# buttons.net
KiCad netlist of a schematic drawn in Altium Designer
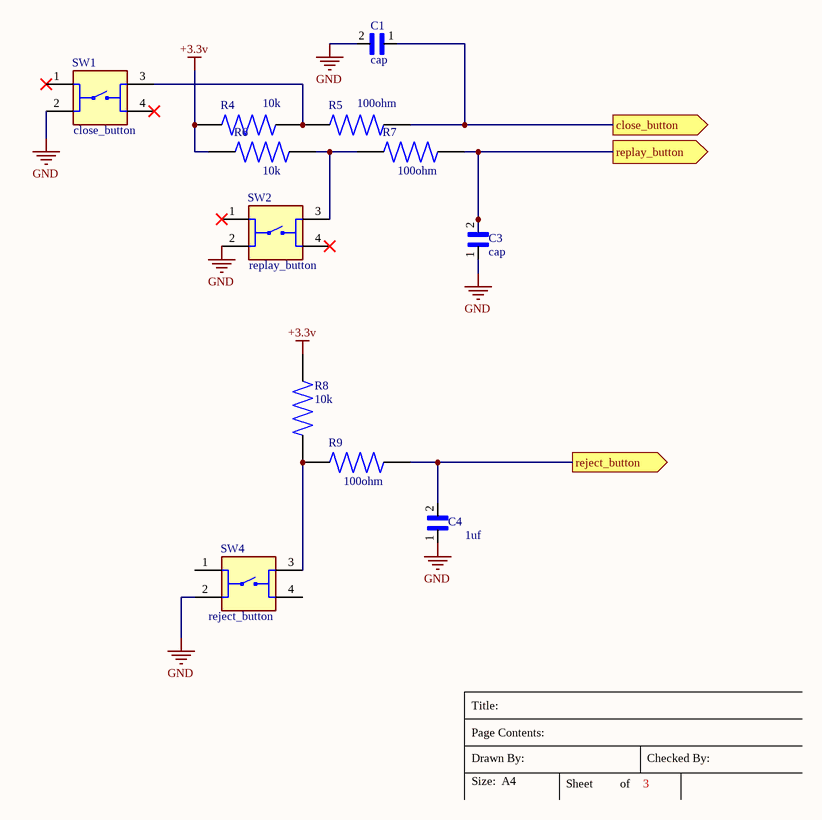
[diagram p0: buttons.SchDoc]

(export (version "E")
  (design (tool "Eeschema 10.0.6"))
  (components
    (comp (ref "C1")
      (value "cap")
      (footprint "cap")
      (description "Lead Capacitor X7R_EIA_ with Capacitance: 0.10F and Rated Voltage: 1000Vdc")
      (fields (field (name "MF") "Murata") (field (name "MP") "RDER73A104K5E1H03A"))
      (libsource (lib "") (part "cap_1"))
    )
    (comp (ref "C3")
      (value "cap")
      (footprint "cap")
      (description "Lead Capacitor X7R_EIA_ with Capacitance: 0.10F and Rated Voltage: 1000Vdc")
      (fields (field (name "MF") "Murata") (field (name "MP") "RDER73A104K5E1H03A"))
      (libsource (lib "Schlib_circuit_de_puissance") (part "cap"))
    )
    (comp (ref "C4")
      (value "1uf")
      (footprint "cap")
      (description "Lead Capacitor X7R_EIA_ with Capacitance: 0.10F and Rated Voltage: 1000Vdc")
      (fields (field (name "MF") "Murata") (field (name "MP") "RDER73A104K5E1H03A"))
      (libsource (lib "Schlib_circuit_de_puissance") (part "cap"))
    )
    (comp (ref "R4")
      (value "10k")
      (footprint "resistance")
      (fields
        (field (name "MP") "CBT50J5R1")
        (field (name "MF") "TE Connectivity / AMP")
        (field (name "Comment") "resistance")
      )
      (libsource (lib "Schlib_circuit_de_puissance") (part "resistance"))
    )
    (comp (ref "R5")
      (value "100ohm")
      (footprint "resistance")
      (fields
        (field (name "MP") "CBT50J5R1")
        (field (name "MF") "TE Connectivity / AMP")
        (field (name "Comment") "resistance")
      )
      (libsource (lib "Schlib_circuit_de_puissance") (part "resistance"))
    )
    (comp (ref "R6")
      (value "10k")
      (footprint "resistance")
      (fields
        (field (name "MP") "CBT50J5R1")
        (field (name "MF") "TE Connectivity / AMP")
        (field (name "Comment") "resistance")
      )
      (libsource (lib "Schlib_circuit_de_puissance") (part "resistance"))
    )
    (comp (ref "R7")
      (value "100ohm")
      (footprint "resistance")
      (fields
        (field (name "MP") "CBT50J5R1")
        (field (name "MF") "TE Connectivity / AMP")
        (field (name "Comment") "resistance")
      )
      (libsource (lib "Schlib_circuit_de_puissance") (part "resistance"))
    )
    (comp (ref "R8")
      (value "10k")
      (footprint "resistance")
      (fields
        (field (name "MP") "CBT50J5R1")
        (field (name "MF") "TE Connectivity / AMP")
        (field (name "Comment") "resistance")
      )
      (libsource (lib "Schlib_circuit_de_puissance") (part "resistance"))
    )
    (comp (ref "R9")
      (value "100ohm")
      (footprint "resistance")
      (fields
        (field (name "MP") "CBT50J5R1")
        (field (name "MF") "TE Connectivity / AMP")
        (field (name "Comment") "resistance")
      )
      (libsource (lib "Schlib_circuit_de_puissance") (part "resistance"))
    )
    (comp (ref "SW1")
      (value "close_button")
      (footprint "push_button_pcb")
      (description "Switch Push Button OFF (ON) SPST Round Button 0.05A 24VDC Momentary Contact PC Pins Thru-Hole")
      (fields (field (name "MP") "1825910-6") (field (name "MF") "TE Connectivity"))
      (libsource (lib "Schlib_circuit_de_puissance") (part "push_button"))
    )
    (comp (ref "SW2")
      (value "replay_button")
      (footprint "push_button_pcb")
      (description "Switch Push Button OFF (ON) SPST Round Button 0.05A 24VDC Momentary Contact PC Pins Thru-Hole")
      (fields (field (name "MP") "1825910-6") (field (name "MF") "TE Connectivity"))
      (libsource (lib "Schlib_circuit_de_puissance") (part "push_button"))
    )
    (comp (ref "SW4")
      (value "reject_button")
      (footprint "push_button_pcb")
      (description "Switch Push Button OFF (ON) SPST Round Button 0.05A 24VDC Momentary Contact PC Pins Thru-Hole")
      (fields (field (name "MP") "1825910-6") (field (name "MF") "TE Connectivity"))
      (libsource (lib "Schlib_circuit_de_puissance") (part "push_button"))
    )
  )
  (nets
    (net (code "1") (name "+3.3v") (class "Default")
      (node (ref "R4") (pin "2") (pinfunction "2_2") (pintype "passive"))
      (node (ref "R6") (pin "2") (pinfunction "2_2") (pintype "passive"))
      (node (ref "R8") (pin "1") (pinfunction "1_1") (pintype "passive"))
    )
    (net (code "2") (name "/close_button") (class "Default")
      (node (ref "C1") (pin "1") (pinfunction "1_1") (pintype "passive"))
      (node (ref "R5") (pin "1") (pinfunction "1_1") (pintype "passive"))
    )
    (net (code "3") (name "/reject_button") (class "Default")
      (node (ref "C4") (pin "2") (pinfunction "2_2") (pintype "passive"))
      (node (ref "R9") (pin "1") (pinfunction "1_1") (pintype "passive"))
    )
    (net (code "4") (name "/replay_button") (class "Default")
      (node (ref "C3") (pin "2") (pinfunction "2_2") (pintype "passive"))
      (node (ref "R7") (pin "1") (pinfunction "1_1") (pintype "passive"))
    )
    (net (code "5") (name "GND") (class "Default")
      (node (ref "C1") (pin "2") (pinfunction "2_2") (pintype "passive"))
      (node (ref "C3") (pin "1") (pinfunction "1_1") (pintype "passive"))
      (node (ref "C4") (pin "1") (pinfunction "1_1") (pintype "passive"))
      (node (ref "SW1") (pin "2") (pinfunction "2_2") (pintype "passive"))
      (node (ref "SW2") (pin "2") (pinfunction "2_2") (pintype "passive"))
      (node (ref "SW4") (pin "2") (pinfunction "2_2") (pintype "passive"))
    )
    (net (code "6") (name "Net-(R4-Pad1)") (class "Default")
      (node (ref "R4") (pin "1") (pinfunction "1_1") (pintype "passive"))
      (node (ref "R5") (pin "2") (pinfunction "2_2") (pintype "passive"))
      (node (ref "SW1") (pin "3") (pinfunction "3_3") (pintype "passive"))
    )
    (net (code "7") (name "Net-(R6-Pad1)") (class "Default")
      (node (ref "R6") (pin "1") (pinfunction "1_1") (pintype "passive"))
      (node (ref "R7") (pin "2") (pinfunction "2_2") (pintype "passive"))
      (node (ref "SW2") (pin "3") (pinfunction "3_3") (pintype "passive"))
    )
    (net (code "8") (name "Net-(R8-Pad2)") (class "Default")
      (node (ref "R8") (pin "2") (pinfunction "2_2") (pintype "passive"))
      (node (ref "R9") (pin "2") (pinfunction "2_2") (pintype "passive"))
      (node (ref "SW4") (pin "3") (pinfunction "3_3") (pintype "passive"))
    )
    (net (code "9") (name "unconnected-(SW1-Pad1)") (class "Default")
      (node (ref "SW1") (pin "1") (pinfunction "1_1") (pintype "passive+no_connect"))
    )
    (net (code "10") (name "unconnected-(SW1-Pad4)") (class "Default")
      (node (ref "SW1") (pin "4") (pinfunction "4_4") (pintype "passive+no_connect"))
    )
    (net (code "11") (name "unconnected-(SW2-Pad1)") (class "Default")
      (node (ref "SW2") (pin "1") (pinfunction "1_1") (pintype "passive+no_connect"))
    )
    (net (code "12") (name "unconnected-(SW2-Pad4)") (class "Default")
      (node (ref "SW2") (pin "4") (pinfunction "4_4") (pintype "passive+no_connect"))
    )
    (net (code "13") (name "unconnected-(SW4-Pad1)") (class "Default")
      (node (ref "SW4") (pin "1") (pinfunction "1_1") (pintype "passive"))
    )
    (net (code "14") (name "unconnected-(SW4-Pad4)") (class "Default")
      (node (ref "SW4") (pin "4") (pinfunction "4_4") (pintype "passive"))
    )
  )
)
